# 11_Power-DC_IN.net
KiCad netlist of a schematic drawn in Altium Designer
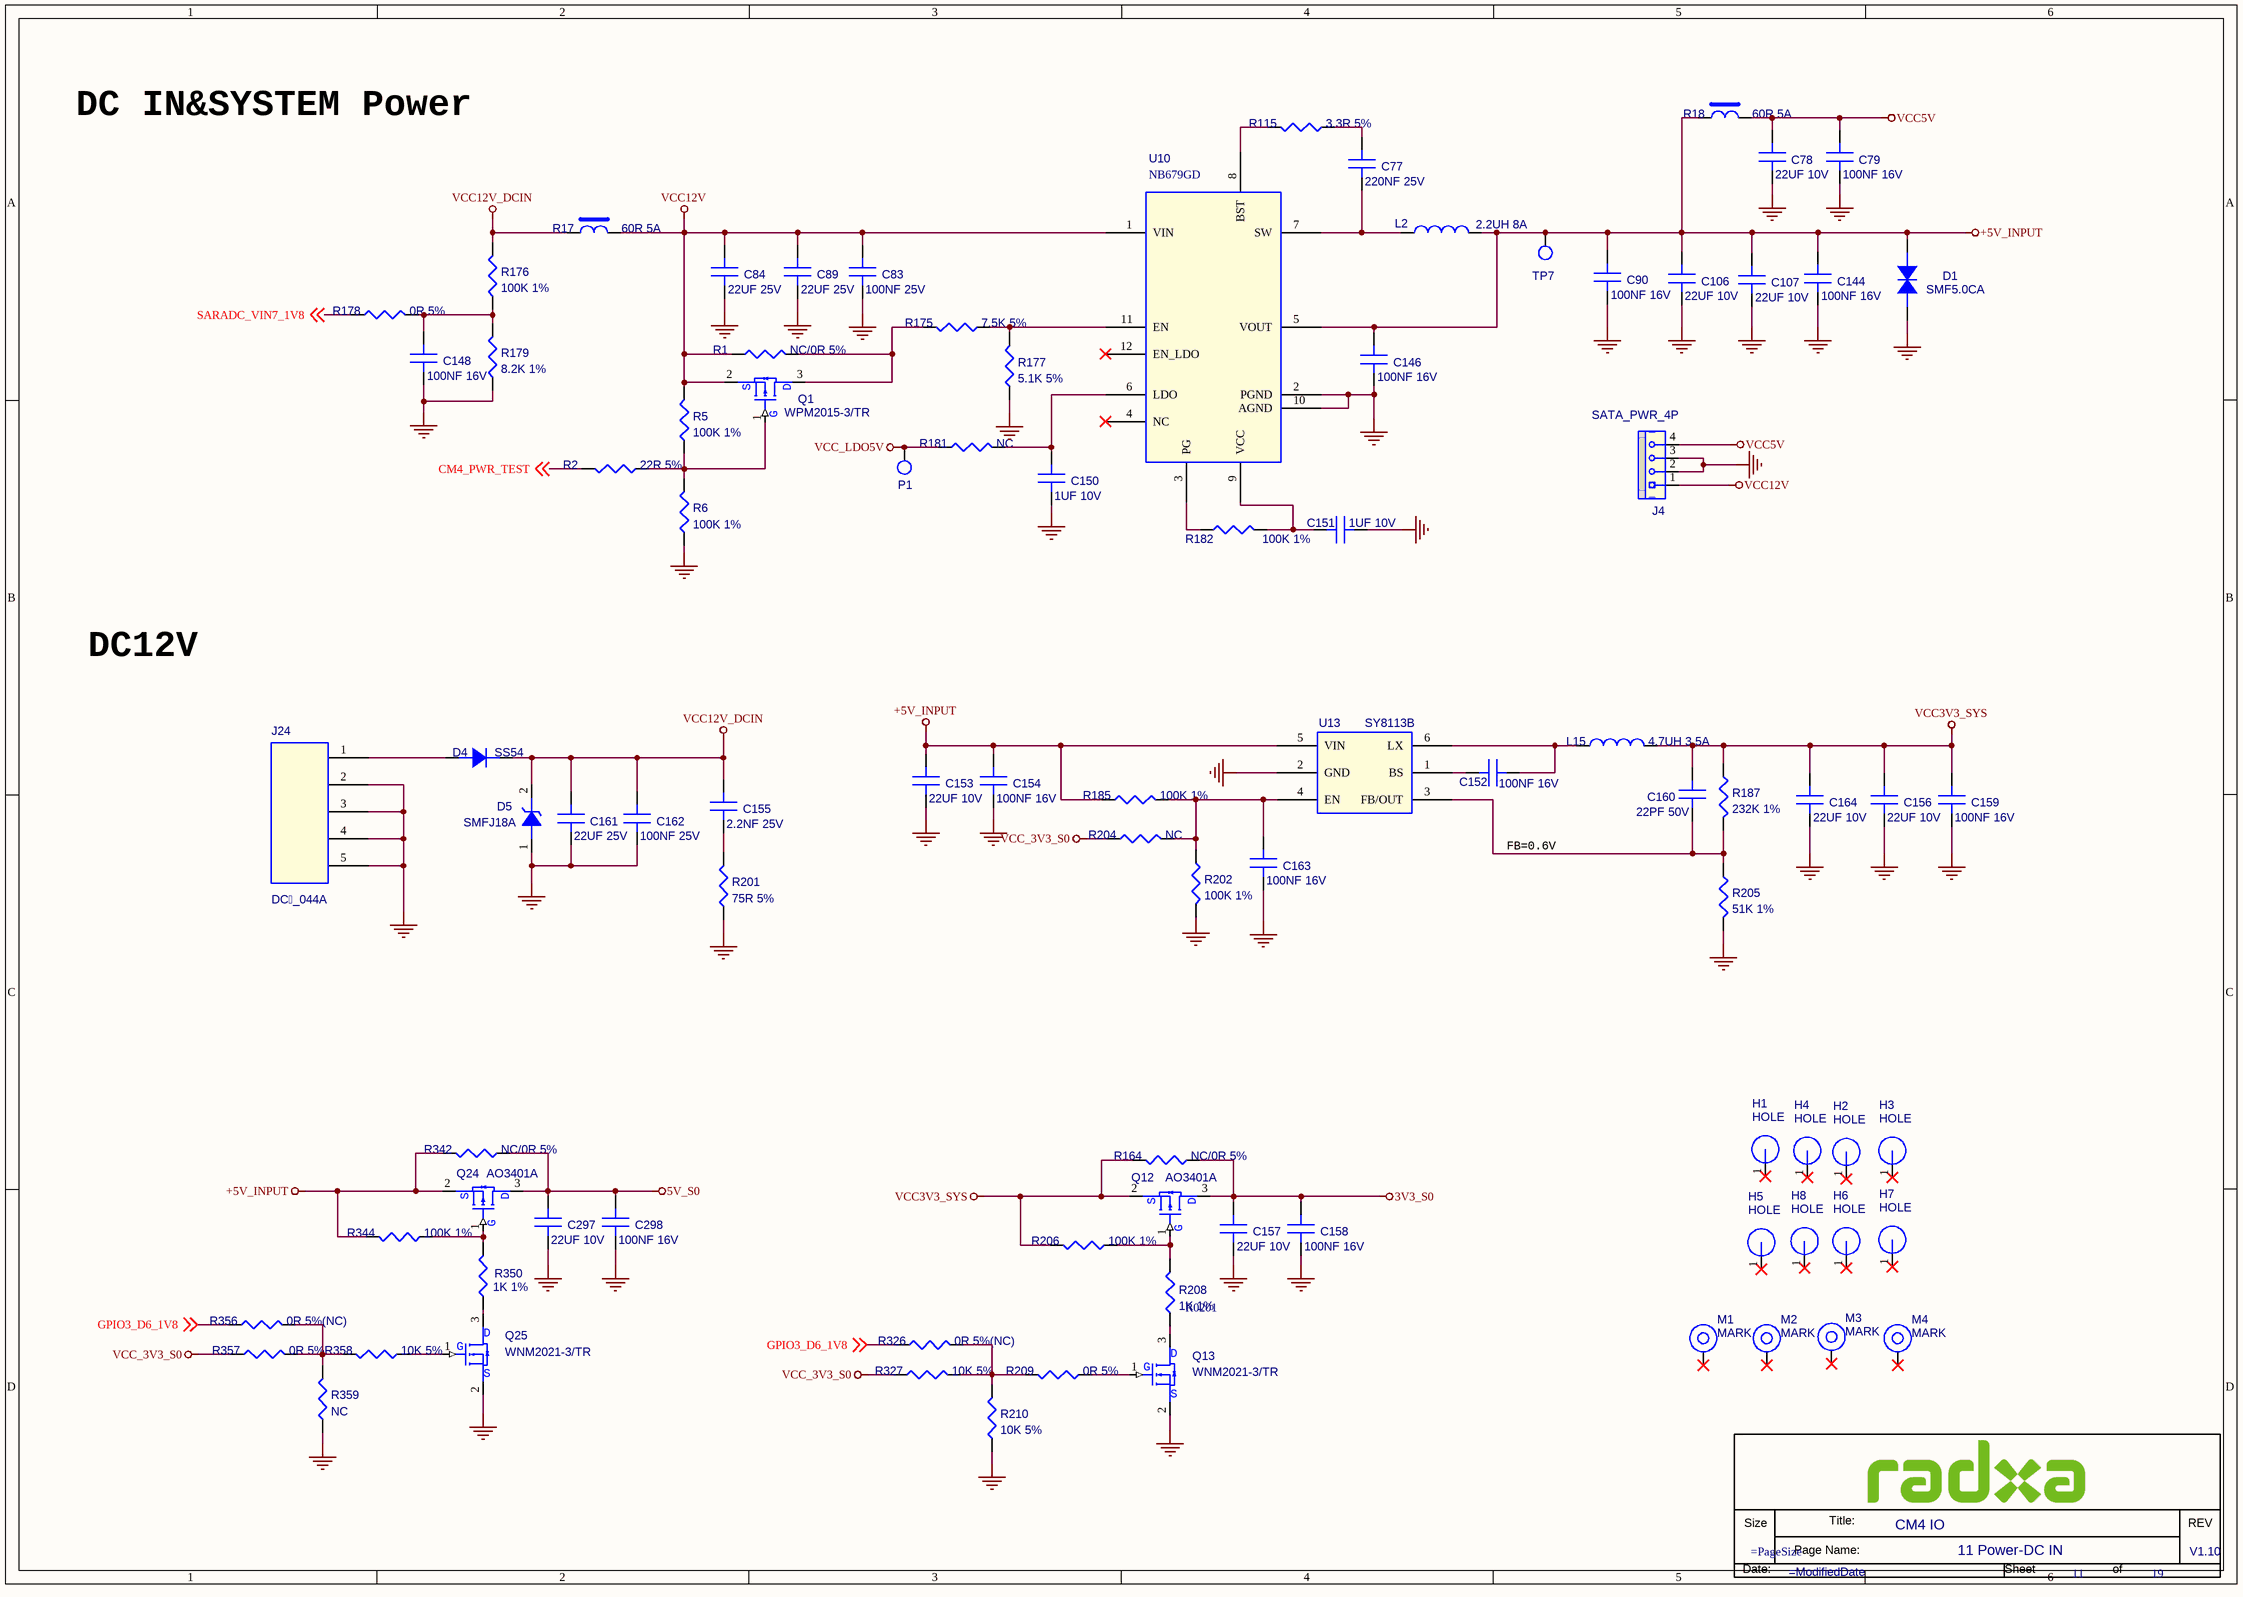
[diagram p0: 11 Power-DC IN.SchDoc]

(export (version "E")
  (design (tool "Eeschema 10.0.6"))
  (components
    (comp (ref "C77")
      (value "220NF 25V")
      (footprint "C0201")
      (description "SMD  0201  220NF  25V  X5R  ±10%  ROHS")
      (fields (field (name "PART NUMBER") "A1C01.00365"))
      (libsource (lib "*") (part "C"))
    )
    (comp (ref "C78")
      (value "22UF 10V")
      (footprint "C0603")
      (description "SMD  0603  22UF  10V  X5R  ±20%  ROHS")
      (fields (field (name "PART NUMBER") "A1C01.00015"))
      (libsource (lib "*") (part "C"))
    )
    (comp (ref "C79")
      (value "100NF 16V")
      (footprint "C0201")
      (description "SMD  0201  100NF  16V  X5R  ±20%  ROHS")
      (fields (field (name "PART NUMBER") "A1C01.00099"))
      (libsource (lib "*") (part "C"))
    )
    (comp (ref "C83")
      (value "100NF 25V")
      (footprint "C0201")
      (description "SMD  0201  100NF  25V  X5R  ±20%  ROHS")
      (fields (field (name "PART NUMBER") "A1C01.00101"))
      (libsource (lib "*") (part "C"))
    )
    (comp (ref "C84")
      (value "22UF 25V")
      (footprint "C0805")
      (description "SMD  0805  22UF  25V  X5R  ±20%  ROHS")
      (fields (field (name "PART NUMBER") "A1C01.00249"))
      (libsource (lib "*") (part "C"))
    )
    (comp (ref "C89")
      (value "22UF 25V")
      (footprint "C0805")
      (description "SMD  0805  22UF  25V  X5R  ±20%  ROHS")
      (fields (field (name "PART NUMBER") "A1C01.00249"))
      (libsource (lib "*") (part "C"))
    )
    (comp (ref "C90")
      (value "100NF 16V")
      (footprint "C0201")
      (description "SMD  0201  100NF  16V  X5R  ±20%  ROHS")
      (fields (field (name "PART NUMBER") "A1C01.00099"))
      (libsource (lib "*") (part "C"))
    )
    (comp (ref "C106")
      (value "22UF 10V")
      (footprint "C0603")
      (description "SMD  0603  22UF  10V  X5R  ±20%  ROHS")
      (fields (field (name "PART NUMBER") "A1C01.00015"))
      (libsource (lib "*") (part "C"))
    )
    (comp (ref "C107")
      (value "22UF 10V")
      (footprint "C0603")
      (description "SMD  0603  22UF  10V  X5R  ±20%  ROHS")
      (fields (field (name "PART NUMBER") "A1C01.00015"))
      (libsource (lib "*") (part "C"))
    )
    (comp (ref "C144")
      (value "100NF 16V")
      (footprint "C0201")
      (description "SMD  0201  100NF  16V  X5R  ±20%  ROHS")
      (fields (field (name "PART NUMBER") "A1C01.00099"))
      (libsource (lib "*") (part "C"))
    )
    (comp (ref "C146")
      (value "100NF 16V")
      (footprint "C0201")
      (description "SMD  0201  100NF  16V  X5R  ±20%  ROHS")
      (fields (field (name "PART NUMBER") "A1C01.00099"))
      (libsource (lib "*") (part "C"))
    )
    (comp (ref "C148")
      (value "100NF 16V")
      (footprint "C0201")
      (description "SMD  0201  100NF  16V  X5R  ±20%  ROHS")
      (fields (field (name "PART NUMBER") "A1C01.00099"))
      (libsource (lib "*") (part "C"))
    )
    (comp (ref "C150")
      (value "1UF 10V")
      (footprint "C0201")
      (description "SMD  0201  1UF  10V  X5R  ±20%  ROHS")
      (fields (field (name "PART NUMBER") "A1C01.00081"))
      (libsource (lib "*") (part "C"))
    )
    (comp (ref "C151")
      (value "1UF 10V")
      (footprint "C0201")
      (description "SMD  0201  1UF  10V  X5R  ±20%  ROHS")
      (fields (field (name "PART NUMBER") "A1C01.00081"))
      (libsource (lib "*") (part "C"))
    )
    (comp (ref "C152")
      (value "100NF 16V")
      (footprint "C0201")
      (description "SMD  0201  100NF  16V  X5R  ±20%  ROHS")
      (fields (field (name "PART NUMBER") "A1C01.00099"))
      (libsource (lib "*") (part "C"))
    )
    (comp (ref "C153")
      (value "22UF 10V")
      (footprint "C0603")
      (description "SMD  0603  22UF  10V  X5R  ±20%  ROHS")
      (fields (field (name "PART NUMBER") "A1C01.00015"))
      (libsource (lib "*") (part "C"))
    )
    (comp (ref "C154")
      (value "100NF 16V")
      (footprint "C0201")
      (description "SMD  0201  100NF  16V  X5R  ±20%  ROHS")
      (fields (field (name "PART NUMBER") "A1C01.00099"))
      (libsource (lib "*") (part "C"))
    )
    (comp (ref "C155")
      (value "2.2NF 25V")
      (footprint "C0201")
      (description "SMD  0201  2.2NF  25V  X7R  ±10%  ROHS")
      (fields (field (name "PART NUMBER") "A1C01.00123"))
      (libsource (lib "*") (part "C"))
    )
    (comp (ref "C156")
      (value "22UF 10V")
      (footprint "C0603")
      (description "SMD  0603  22UF  10V  X5R  ±20%  ROHS")
      (fields (field (name "PART NUMBER") "A1C01.00015"))
      (libsource (lib "*") (part "C"))
    )
    (comp (ref "C157")
      (value "22UF 10V")
      (footprint "C0603")
      (description "SMD  0603  22UF  10V  X5R  ±20%  ROHS")
      (fields (field (name "PART NUMBER") "A1C01.00015"))
      (libsource (lib "*") (part "C"))
    )
    (comp (ref "C158")
      (value "100NF 16V")
      (footprint "C0201")
      (description "SMD  0201  100NF  16V  X5R  ±20%  ROHS")
      (fields (field (name "PART NUMBER") "A1C01.00099"))
      (libsource (lib "*") (part "C"))
    )
    (comp (ref "C159")
      (value "100NF 16V")
      (footprint "C0201")
      (description "SMD  0201  100NF  16V  X5R  ±20%  ROHS")
      (fields (field (name "PART NUMBER") "A1C01.00099"))
      (libsource (lib "*") (part "C"))
    )
    (comp (ref "C160")
      (value "22PF 50V")
      (footprint "C0201")
      (description "SMD  0201  22PF  50V  NPO  ±5%  ROHS")
      (fields (field (name "PART NUMBER") "A1C01.00021"))
      (libsource (lib "*") (part "C"))
    )
    (comp (ref "C161")
      (value "22UF 25V")
      (footprint "C0805")
      (description "SMD  0805  22UF  25V  X5R  ±20%  ROHS")
      (fields (field (name "PART NUMBER") "A1C01.00249"))
      (libsource (lib "*") (part "C"))
    )
    (comp (ref "C162")
      (value "100NF 25V")
      (footprint "C0201")
      (description "SMD  0201  100NF  25V  X5R  ±20%  ROHS")
      (fields (field (name "PART NUMBER") "A1C01.00101"))
      (libsource (lib "*") (part "C"))
    )
    (comp (ref "C163")
      (value "100NF 16V")
      (footprint "C0201")
      (description "SMD  0201  100NF  16V  X5R  ±20%  ROHS")
      (fields (field (name "PART NUMBER") "A1C01.00099"))
      (libsource (lib "*") (part "C"))
    )
    (comp (ref "C164")
      (value "22UF 10V")
      (footprint "C0603")
      (description "SMD  0603  22UF  10V  X5R  ±20%  ROHS")
      (fields (field (name "PART NUMBER") "A1C01.00015"))
      (libsource (lib "*") (part "C"))
    )
    (comp (ref "C297")
      (value "22UF 10V")
      (footprint "C0603")
      (description "SMD  0603  22UF  10V  X5R  ±20%  ROHS")
      (fields (field (name "PART NUMBER") "A1C01.00015"))
      (libsource (lib "*") (part "C"))
    )
    (comp (ref "C298")
      (value "100NF 16V")
      (footprint "C0201")
      (description "SMD  0201  100NF  16V  X5R  ±20%  ROHS")
      (fields (field (name "PART NUMBER") "A1C01.00099"))
      (libsource (lib "*") (part "C"))
    )
    (comp (ref "D1")
      (value "SMF5.0CA")
      (footprint "SOD_123")
      (description "SMD  SOD-123FL  SMF5.0CA  晶导微  ROHS")
      (fields (field (name "PART NUMBER") "A1D02.00132"))
      (libsource (lib "*") (part "DIODE_S"))
    )
    (comp (ref "D4")
      (value "SS54")
      (footprint "DO_214AC")
      (description "SMD  编带  DO-214AC  SS54  晶导微  ROHS")
      (fields
        (field (name "MANUFACTURER") "星海")
        (field (name "PART NUMBER") "A1D02.00006")
        (field (name "CREATED BY") "JJJ")
      )
      (libsource (lib "*") (part "DIODE"))
    )
    (comp (ref "D5")
      (value "SMFJ18A")
      (footprint "SOD_123")
      (description "SMD  编带  SOD-123  SMFJ18A  晶导微电子  ROHS")
      (fields (field (name "PART NUMBER") "A1D02.00007"))
      (libsource (lib "*") (part "TVS"))
    )
    (comp (ref "H1")
      (value "HOLE")
      (footprint "H3.8MM")
      (description "直径3.5mm hole")
      (fields (field (name "CREATED BY") "CZD"))
      (libsource (lib "*") (part "HOLE"))
    )
    (comp (ref "H2")
      (value "HOLE")
      (footprint "H3.8MM")
      (description "直径3.5mm hole")
      (fields (field (name "CREATED BY") "CZD"))
      (libsource (lib "*") (part "HOLE"))
    )
    (comp (ref "H3")
      (value "HOLE")
      (footprint "H3.8MM")
      (description "直径3.5mm hole")
      (fields (field (name "CREATED BY") "CZD"))
      (libsource (lib "*") (part "HOLE"))
    )
    (comp (ref "H4")
      (value "HOLE")
      (footprint "H3.8MM")
      (description "直径3.5mm hole")
      (fields (field (name "CREATED BY") "CZD"))
      (libsource (lib "*") (part "HOLE"))
    )
    (comp (ref "H5")
      (value "HOLE")
      (footprint "H3.8MM")
      (description "直径3.5mm hole")
      (fields (field (name "CREATED BY") "CZD"))
      (libsource (lib "*") (part "HOLE"))
    )
    (comp (ref "H6")
      (value "HOLE")
      (footprint "H3.8MM")
      (description "直径3.5mm hole")
      (fields (field (name "CREATED BY") "CZD"))
      (libsource (lib "*") (part "HOLE"))
    )
    (comp (ref "H7")
      (value "HOLE")
      (footprint "H3.8MM")
      (description "直径3.5mm hole")
      (fields (field (name "CREATED BY") "CZD"))
      (libsource (lib "*") (part "HOLE"))
    )
    (comp (ref "H8")
      (value "HOLE")
      (footprint "H3.8MM")
      (description "直径3.5mm hole")
      (fields (field (name "CREATED BY") "CZD"))
      (libsource (lib "*") (part "HOLE"))
    )
    (comp (ref "J4")
      (value "SATA_PWR_4P")
      (footprint "CON_TH1X4_2D54_SATA")
      (description "DIP  排针座  1*4PIN  180度  无定位柱  2.54mm脚距  针长一端8.3mm  另一端3.5mm  小4PIN  白色  M2545V-4P  兴飞  ROHS")
      (fields (field (name "PART NUMBER") "A1J01.00014"))
      (libsource (lib "*") (part "SATA_PWR_4P"))
    )
    (comp (ref "J24")
      (value "DC_044A")
      (footprint "DC_TH5_12X10")
      (description "DIP  5PIN  DS-044BS  内孔Φ6mm  铁芯Φ2.0mm  11.6*10.2*7.3mm  协佳  ROHS")
      (fields (field (name "PART NUMBER") "A1J11.00007"))
      (libsource (lib "*") (part "DC_044A_5520"))
    )
    (comp (ref "L2")
      (value "2.2UH 8A")
      (footprint "L_6050")
      (description "SMD  带屏蔽  7.2x6.6x5mm  2.2UH  8A  ±20%  RXWSHC0650-2R2M  仁芯微  ROHS")
      (fields (field (name "PART NUMBER") "A1L01.00163"))
      (libsource (lib "*") (part "L"))
    )
    (comp (ref "L15")
      (value "4.7UH 3.5A")
      (footprint "L_5020")
      (description "SMD  带屏蔽  5.4*5.2*1.8mm  4.7UH  3.5A  ±20%  RXWSHC0520-4R7M  仁芯微  ROHS")
      (fields (field (name "PART NUMBER") "A1L01.00071"))
      (libsource (lib "*") (part "L"))
    )
    (comp (ref "M1")
      (value "MARK")
      (footprint "MARK")
      (description "MARK Symble")
      (fields (field (name "CREATED BY") "JJJ"))
      (libsource (lib "*") (part "MARK"))
    )
    (comp (ref "M2")
      (value "MARK")
      (footprint "MARK")
      (description "MARK Symble")
      (fields (field (name "CREATED BY") "JJJ"))
      (libsource (lib "*") (part "MARK"))
    )
    (comp (ref "M3")
      (value "MARK")
      (footprint "MARK")
      (description "MARK Symble")
      (fields (field (name "CREATED BY") "JJJ"))
      (libsource (lib "*") (part "MARK"))
    )
    (comp (ref "M4")
      (value "MARK")
      (footprint "MARK")
      (description "MARK Symble")
      (fields (field (name "CREATED BY") "JJJ"))
      (libsource (lib "*") (part "MARK"))
    )
    (comp (ref "P1") (value "TEST") (footprint "TEST") (libsource (lib "*") (part "TESTPOINT1")))
    (comp (ref "Q1")
      (value "WPM2015-3/TR")
      (footprint "SOT_23")
      (description "SMD编带  SOT-23  WPM2015-3/TR  P沟道  ROHS")
      (fields (field (name "PART NUMBER") "A1D01.00019"))
      (libsource (lib "*") (part "MOSFET_PNP"))
    )
    (comp (ref "Q12")
      (value "AO3401A")
      (footprint "SOT_23")
      (description "SMD  编带  SOT23-3  AO3401A  P沟道  AOS  ROHS")
      (fields (field (name "PART NUMBER") "A1D01.00034"))
      (libsource (lib "*") (part "MOSFET_PNP"))
    )
    (comp (ref "Q13")
      (value "WNM2021-3/TR")
      (footprint "SOT_323")
      (description "SMD编带  SOT-323  WILLSEMI(韦尔)  WNM2021-3/TR  N沟道  ROHS")
      (fields (field (name "PART NUMBER") "A1D01.00008"))
      (libsource (lib "*") (part "MOSFET_NPN"))
    )
    (comp (ref "Q24")
      (value "AO3401A")
      (footprint "SOT_23")
      (description "SMD  编带  SOT23-3  AO3401A  P沟道  AOS  ROHS")
      (fields (field (name "PART NUMBER") "A1D01.00034"))
      (libsource (lib "*") (part "MOSFET_PNP"))
    )
    (comp (ref "Q25")
      (value "WNM2021-3/TR")
      (footprint "SOT_323")
      (description "SMD编带  SOT-323  WILLSEMI(韦尔)  WNM2021-3/TR  N沟道  ROHS")
      (fields (field (name "PART NUMBER") "A1D01.00008"))
      (libsource (lib "*") (part "MOSFET_NPN"))
    )
    (comp (ref "R1")
      (value "NC/0R 5%")
      (footprint "R0402")
      (description "SMD  0201  0R  1/20W  ±5%  ROHS")
      (fields (field (name "PART NUMBER") "A1R01.00027"))
      (libsource (lib "*") (part "R"))
    )
    (comp (ref "R2")
      (value "22R 5%")
      (footprint "R0402")
      (description "SMD  0201  22R  1/20W  ±5%  ROHS")
      (fields (field (name "PART NUMBER") "A1R01.00024"))
      (libsource (lib "*") (part "R"))
    )
    (comp (ref "R5")
      (value "100K 1%")
      (footprint "R0402")
      (description "SMD  0201  100K  1/20W  ±1%  ROHS")
      (fields (field (name "PART NUMBER") "A1R01.00165"))
      (libsource (lib "*") (part "R"))
    )
    (comp (ref "R6")
      (value "100K 1%")
      (footprint "R0402")
      (description "SMD  0201  100K  1/20W  ±1%  ROHS")
      (fields (field (name "PART NUMBER") "A1R01.00165"))
      (libsource (lib "*") (part "R"))
    )
    (comp (ref "R17")
      (value "60R 5A")
      (footprint "FB1206")
      (description "SMD  1206  FB60R  5A  ±25%  ROHS")
      (fields (field (name "PART NUMBER") "A1L09.00006"))
      (libsource (lib "*") (part "BEAD"))
    )
    (comp (ref "R18")
      (value "60R 5A")
      (footprint "FB1206")
      (description "SMD  1206  FB60R  5A  ±25%  ROHS")
      (fields (field (name "PART NUMBER") "A1L09.00006"))
      (libsource (lib "*") (part "BEAD"))
    )
    (comp (ref "R115")
      (value "3.3R 5%")
      (footprint "R0402")
      (description "SMD  0201  3.3R  1/20W  ±5%  ROHS")
      (fields (field (name "PART NUMBER") "A1R01.00145"))
      (libsource (lib "*") (part "R"))
    )
    (comp (ref "R164")
      (value "NC/0R 5%")
      (footprint "R0402")
      (description "SMD  0402  0R  1/16W  ±5%  ROHS")
      (fields (field (name "PART NUMBER") "A1R01.00030"))
      (libsource (lib "*") (part "R"))
    )
    (comp (ref "R175")
      (value "7.5K 5%")
      (footprint "R0402")
      (description "SMD  0201  7.5K  1/20W  ±5%  ROHS")
      (fields (field (name "PART NUMBER") "A1R01.00495"))
      (libsource (lib "*") (part "R"))
    )
    (comp (ref "R176")
      (value "100K 1%")
      (footprint "R0402")
      (description "SMD  0201  100K  1/20W  ±1%  ROHS")
      (fields (field (name "PART NUMBER") "A1R01.00165"))
      (libsource (lib "*") (part "R"))
    )
    (comp (ref "R177")
      (value "5.1K 5%")
      (footprint "R0402")
      (description "SMD  0201  5.1K  1/20W  ±5%  ROHS")
      (fields (field (name "PART NUMBER") "A1R01.00013"))
      (libsource (lib "*") (part "R"))
    )
    (comp (ref "R178")
      (value "0R 5%")
      (footprint "R0402")
      (description "SMD  0201  0R  1/20W  ±5%  ROHS")
      (fields (field (name "PART NUMBER") "A1R01.00027"))
      (libsource (lib "*") (part "R"))
    )
    (comp (ref "R179")
      (value "8.2K 1%")
      (footprint "R0402")
      (description "SMD  0201  8.2K  1/20W  ±1%  ROHS")
      (fields (field (name "PART NUMBER") "A1R01.00086"))
      (libsource (lib "*") (part "R"))
    )
    (comp (ref "R181")
      (value "NC")
      (footprint "R0402")
      (description "SMD  0201  0R  1/20W  ±5%  ROHS")
      (fields (field (name "PART NUMBER") "A1R01.00027"))
      (libsource (lib "*") (part "R"))
    )
    (comp (ref "R182")
      (value "100K 1%")
      (footprint "R0402")
      (description "SMD  0201  100K  1/20W  ±1%  ROHS")
      (fields (field (name "PART NUMBER") "A1R01.00165"))
      (libsource (lib "*") (part "R"))
    )
    (comp (ref "R185")
      (value "100K 1%")
      (footprint "R0402")
      (description "SMD  0201  100K  1/20W  ±1%  ROHS")
      (fields (field (name "PART NUMBER") "A1R01.00165"))
      (libsource (lib "*") (part "R"))
    )
    (comp (ref "R187")
      (value "232K 1%")
      (footprint "R0402")
      (description "SMD  0201  232K  1/20W  ±1%  ROHS")
      (fields (field (name "PART NUMBER") "A1R01.00189"))
      (libsource (lib "*") (part "R"))
    )
    (comp (ref "R201")
      (value "75R 5%")
      (footprint "R0402")
      (description "SMD  0201  75R  1/20W  ±5%  ROHS")
      (fields (field (name "PART NUMBER") "A1R01.00395"))
      (libsource (lib "*") (part "R"))
    )
    (comp (ref "R202")
      (value "100K 1%")
      (footprint "R0402")
      (description "SMD  0201  100K  1/20W  ±1%  ROHS")
      (fields (field (name "PART NUMBER") "A1R01.00165"))
      (libsource (lib "*") (part "R"))
    )
    (comp (ref "R204")
      (value "NC")
      (footprint "R0402")
      (description "SMD  0201  10K  1/20W  ±5%  ROHS")
      (fields (field (name "PART NUMBER") "A1R01.00012"))
      (libsource (lib "*") (part "R"))
    )
    (comp (ref "R205")
      (value "51K 1%")
      (footprint "R0402")
      (description "SMD  0201  51K  1/20W  ±1%  ROHS")
      (fields (field (name "PART NUMBER") "A1R01.00149"))
      (libsource (lib "*") (part "R"))
    )
    (comp (ref "R206")
      (value "100K 1%")
      (footprint "R0402")
      (description "SMD  0201  100K  1/20W  ±1%  ROHS")
      (fields (field (name "PART NUMBER") "A1R01.00165"))
      (libsource (lib "*") (part "R"))
    )
    (comp (ref "R208")
      (value "1K 1%")
      (footprint "R0402")
      (description "SMD  0201  1K  1/20W  ±1%  ROHS")
      (fields (field (name "PCB FOOTPRINT") "R0201") (field (name "PART NUMBER") "A1R01.00111"))
      (libsource (lib "*") (part "R"))
    )
    (comp (ref "R209")
      (value "0R 5%")
      (footprint "R0402")
      (description "SMD  0201  10K  1/20W  ±5%  ROHS")
      (fields (field (name "PART NUMBER") "A1R01.00012"))
      (libsource (lib "*") (part "R"))
    )
    (comp (ref "R210")
      (value "10K 5%")
      (footprint "R0402")
      (description "SMD  0201  10K  1/20W  ±5%  ROHS")
      (fields (field (name "PART NUMBER") "A1R01.00012"))
      (libsource (lib "*") (part "R"))
    )
    (comp (ref "R326")
      (value "0R 5%(NC)")
      (footprint "R0402")
      (description "SMD  0201  0R  1/20W  ±5%  ROHS")
      (fields (field (name "PART NUMBER") "A1R01.00027"))
      (libsource (lib "*") (part "R"))
    )
    (comp (ref "R327")
      (value "10K 5%")
      (footprint "R0402")
      (description "SMD  0201  0R  1/20W  ±5%  ROHS")
      (fields (field (name "PART NUMBER") "A1R01.00027"))
      (libsource (lib "*") (part "R"))
    )
    (comp (ref "R342")
      (value "NC/0R 5%")
      (footprint "R0402")
      (description "SMD  0402  0R  1/16W  ±5%  ROHS")
      (fields (field (name "PART NUMBER") "A1R01.00030"))
      (libsource (lib "*") (part "R"))
    )
    (comp (ref "R344")
      (value "100K 1%")
      (footprint "R0402")
      (description "SMD  0201  100K  1/20W  ±1%  ROHS")
      (fields (field (name "PART NUMBER") "A1R01.00165"))
      (libsource (lib "*") (part "R"))
    )
    (comp (ref "R350")
      (value "1K 1%")
      (footprint "R0402")
      (description "SMD  0201  1K  1/20W  ±1%  ROHS")
      (fields (field (name "PART NUMBER") "A1R01.00111"))
      (libsource (lib "*") (part "R"))
    )
    (comp (ref "R356")
      (value "0R 5%(NC)")
      (footprint "R0402")
      (description "SMD  0201  0R  1/20W  ±5%  ROHS")
      (fields (field (name "PART NUMBER") "A1R01.00027"))
      (libsource (lib "*") (part "R"))
    )
    (comp (ref "R357")
      (value "0R 5%")
      (footprint "R0402")
      (description "SMD  0201  0R  1/20W  ±5%  ROHS")
      (fields (field (name "PART NUMBER") "A1R01.00027"))
      (libsource (lib "*") (part "R"))
    )
    (comp (ref "R358")
      (value "10K 5%")
      (footprint "R0402")
      (description "SMD  0201  10K  1/20W  ±5%  ROHS")
      (fields (field (name "PART NUMBER") "A1R01.00012"))
      (libsource (lib "*") (part "R"))
    )
    (comp (ref "R359")
      (value "NC")
      (footprint "R0402")
      (description "SMD  0201  10K  1/20W  ±5%  ROHS")
      (fields (field (name "PART NUMBER") "A1R01.00012"))
      (libsource (lib "*") (part "R"))
    )
    (comp (ref "TP7")
      (value "TP_0.7")
      (footprint "TEST")
      (description "Test Point 0.7mm")
      (fields (field (name "CREATED BY") "JJJ"))
      (libsource (lib "*") (part "TP"))
    )
    (comp (ref "U10")
      (value "NB679GD")
      (footprint "QFN12_0D5_2")
      (description "SMD  DCDC  NB679GD-Z  QFN12  MPS  ROHS")
      (fields (field (name "PART NUMBER") "A1I01.00033"))
      (libsource (lib "*") (part "NB679"))
    )
    (comp (ref "U13")
      (value "SY8113B")
      (footprint "SOT23_6")
      (description "SMD  DCDC  SY8113BADC  SOT23-6  silergy(矽力杰)  ROHS")
      (fields (field (name "PART NUMBER") "A1I01.00093"))
      (libsource (lib "*") (part "SY8113B"))
    )
  )
  (nets
    (net (code "1") (name "+5V_INPUT") (class "Default")
      (node (ref "C106") (pin "1") (pinfunction "A_1") (pintype "passive"))
      (node (ref "C107") (pin "1") (pinfunction "A_1") (pintype "passive"))
      (node (ref "C144") (pin "1") (pinfunction "A_1") (pintype "passive"))
      (node (ref "C146") (pin "1") (pinfunction "A_1") (pintype "passive"))
      (node (ref "C153") (pin "1") (pinfunction "A_1") (pintype "passive"))
      (node (ref "C154") (pin "1") (pinfunction "A_1") (pintype "passive"))
      (node (ref "C90") (pin "1") (pinfunction "A_1") (pintype "passive"))
      (node (ref "D1") (pin "2") (pinfunction "CATHODE_2") (pintype "passive"))
      (node (ref "L2") (pin "2") (pinfunction "2_2") (pintype "passive"))
      (node (ref "Q24") (pin "2") (pinfunction "S_2") (pintype "passive"))
      (node (ref "R18") (pin "1") (pinfunction "1_1") (pintype "passive"))
      (node (ref "R185") (pin "1") (pinfunction "1_1") (pintype "passive"))
      (node (ref "R342") (pin "2") (pinfunction "2_2") (pintype "passive"))
      (node (ref "R344") (pin "2") (pinfunction "2_2") (pintype "passive"))
      (node (ref "TP7") (pin "1") (pinfunction "1_1") (pintype "passive"))
      (node (ref "U10") (pin "5") (pinfunction "VOUT_5") (pintype "passive"))
      (node (ref "U13") (pin "5") (pinfunction "VIN_5") (pintype "passive"))
    )
    (net (code "2") (name "3V3_S0") (class "Default")
      (node (ref "C157") (pin "1") (pinfunction "A_1") (pintype "passive"))
      (node (ref "C158") (pin "1") (pinfunction "A_1") (pintype "passive"))
      (node (ref "Q12") (pin "3") (pinfunction "D_3") (pintype "passive"))
      (node (ref "R164") (pin "1") (pinfunction "1_1") (pintype "passive"))
    )
    (net (code "3") (name "5V_S0") (class "Default")
      (node (ref "C297") (pin "1") (pinfunction "A_1") (pintype "passive"))
      (node (ref "C298") (pin "1") (pinfunction "A_1") (pintype "passive"))
      (node (ref "Q24") (pin "3") (pinfunction "D_3") (pintype "passive"))
      (node (ref "R342") (pin "1") (pinfunction "1_1") (pintype "passive"))
    )
    (net (code "4") (name "CM4_PWR_TEST") (class "Default")
      (node (ref "R2") (pin "1") (pinfunction "1_1") (pintype "passive"))
    )
    (net (code "5") (name "GND") (class "Default")
      (node (ref "C106") (pin "2") (pinfunction "B_2") (pintype "passive"))
      (node (ref "C107") (pin "2") (pinfunction "B_2") (pintype "passive"))
      (node (ref "C144") (pin "2") (pinfunction "B_2") (pintype "passive"))
      (node (ref "C146") (pin "2") (pinfunction "B_2") (pintype "passive"))
      (node (ref "C148") (pin "2") (pinfunction "B_2") (pintype "passive"))
      (node (ref "C150") (pin "2") (pinfunction "B_2") (pintype "passive"))
      (node (ref "C151") (pin "2") (pinfunction "B_2") (pintype "passive"))
      (node (ref "C153") (pin "2") (pinfunction "B_2") (pintype "passive"))
      (node (ref "C154") (pin "2") (pinfunction "B_2") (pintype "passive"))
      (node (ref "C156") (pin "2") (pinfunction "B_2") (pintype "passive"))
      (node (ref "C157") (pin "2") (pinfunction "B_2") (pintype "passive"))
      (node (ref "C158") (pin "2") (pinfunction "B_2") (pintype "passive"))
      (node (ref "C159") (pin "2") (pinfunction "B_2") (pintype "passive"))
      (node (ref "C161") (pin "1") (pinfunction "A_1") (pintype "passive"))
      (node (ref "C162") (pin "2") (pinfunction "B_2") (pintype "passive"))
      (node (ref "C163") (pin "2") (pinfunction "B_2") (pintype "passive"))
      (node (ref "C164") (pin "2") (pinfunction "B_2") (pintype "passive"))
      (node (ref "C297") (pin "2") (pinfunction "B_2") (pintype "passive"))
      (node (ref "C298") (pin "2") (pinfunction "B_2") (pintype "passive"))
      (node (ref "C78") (pin "2") (pinfunction "B_2") (pintype "passive"))
      (node (ref "C79") (pin "2") (pinfunction "B_2") (pintype "passive"))
      (node (ref "C83") (pin "2") (pinfunction "B_2") (pintype "passive"))
      (node (ref "C84") (pin "2") (pinfunction "B_2") (pintype "passive"))
      (node (ref "C89") (pin "2") (pinfunction "B_2") (pintype "passive"))
      (node (ref "C90") (pin "2") (pinfunction "B_2") (pintype "passive"))
      (node (ref "D1") (pin "1") (pinfunction "ANODE_1") (pintype "passive"))
      (node (ref "D5") (pin "1") (pinfunction "ANODE_1") (pintype "passive"))
      (node (ref "J24") (pin "2") (pinfunction "2_2") (pintype "passive"))
      (node (ref "J24") (pin "3") (pinfunction "3_3") (pintype "passive"))
      (node (ref "J24") (pin "4") (pinfunction "4_4") (pintype "passive"))
      (node (ref "J24") (pin "5") (pinfunction "5_5") (pintype "passive"))
      (node (ref "J4") (pin "2") (pinfunction "2_2") (pintype "passive"))
      (node (ref "J4") (pin "3") (pinfunction "3_3") (pintype "passive"))
      (node (ref "Q13") (pin "2") (pinfunction "S_2") (pintype "passive"))
      (node (ref "Q25") (pin "2") (pinfunction "S_2") (pintype "passive"))
      (node (ref "R177") (pin "1") (pinfunction "1_1") (pintype "passive"))
      (node (ref "R179") (pin "1") (pinfunction "1_1") (pintype "passive"))
      (node (ref "R201") (pin "1") (pinfunction "1_1") (pintype "passive"))
      (node (ref "R202") (pin "2") (pinfunction "2_2") (pintype "passive"))
      (node (ref "R205") (pin "2") (pinfunction "2_2") (pintype "passive"))
      (node (ref "R210") (pin "2") (pinfunction "2_2") (pintype "passive"))
      (node (ref "R359") (pin "2") (pinfunction "2_2") (pintype "passive"))
      (node (ref "R6") (pin "1") (pinfunction "1_1") (pintype "passive"))
      (node (ref "U10") (pin "10") (pinfunction "AGND_10") (pintype "passive"))
      (node (ref "U10") (pin "2") (pinfunction "PGND_2") (pintype "passive"))
      (node (ref "U13") (pin "2") (pinfunction "GND_2") (pintype "passive"))
    )
    (net (code "6") (name "GPIO3_D6_1V8") (class "Default")
      (node (ref "R326") (pin "1") (pinfunction "1_1") (pintype "passive"))
      (node (ref "R356") (pin "1") (pinfunction "1_1") (pintype "passive"))
    )
    (net (code "7") (name "Net-(C77-A)") (class "Default")
      (node (ref "C77") (pin "1") (pinfunction "A_1") (pintype "passive"))
      (node (ref "R115") (pin "2") (pinfunction "2_2") (pintype "passive"))
    )
    (net (code "8") (name "Net-(C77-B)") (class "Default")
      (node (ref "C77") (pin "2") (pinfunction "B_2") (pintype "passive"))
      (node (ref "L2") (pin "1") (pinfunction "1_1") (pintype "passive"))
      (node (ref "U10") (pin "7") (pinfunction "SW_7") (pintype "passive"))
    )
    (net (code "9") (name "Net-(C148-A)") (class "Default")
      (node (ref "C148") (pin "1") (pinfunction "A_1") (pintype "passive"))
      (node (ref "R176") (pin "1") (pinfunction "1_1") (pintype "passive"))
      (node (ref "R178") (pin "2") (pinfunction "2_2") (pintype "passive"))
      (node (ref "R179") (pin "2") (pinfunction "2_2") (pintype "passive"))
    )
    (net (code "10") (name "Net-(C150-A)") (class "Default")
      (node (ref "C150") (pin "1") (pinfunction "A_1") (pintype "passive"))
      (node (ref "R181") (pin "2") (pinfunction "2_2") (pintype "passive"))
      (node (ref "U10") (pin "6") (pinfunction "LDO_6") (pintype "passive"))
    )
    (net (code "11") (name "Net-(C151-A)") (class "Default")
      (node (ref "C151") (pin "1") (pinfunction "A_1") (pintype "passive"))
      (node (ref "R182") (pin "2") (pinfunction "2_2") (pintype "passive"))
      (node (ref "U10") (pin "9") (pinfunction "VCC_9") (pintype "passive"))
    )
    (net (code "12") (name "Net-(C152-A)") (class "Default")
      (node (ref "C152") (pin "1") (pinfunction "A_1") (pintype "passive"))
      (node (ref "U13") (pin "1") (pinfunction "BS_1") (pintype "passive"))
    )
    (net (code "13") (name "Net-(C152-B)") (class "Default")
      (node (ref "C152") (pin "2") (pinfunction "B_2") (pintype "passive"))
      (node (ref "L15") (pin "1") (pinfunction "1_1") (pintype "passive"))
      (node (ref "U13") (pin "6") (pinfunction "LX_6") (pintype "passive"))
    )
    (net (code "14") (name "Net-(C155-B)") (class "Default")
      (node (ref "C155") (pin "2") (pinfunction "B_2") (pintype "passive"))
      (node (ref "R201") (pin "2") (pinfunction "2_2") (pintype "passive"))
    )
    (net (code "15") (name "Net-(C160-B)") (class "Default")
      (node (ref "C160") (pin "2") (pinfunction "B_2") (pintype "passive"))
      (node (ref "R187") (pin "2") (pinfunction "2_2") (pintype "passive"))
      (node (ref "R205") (pin "1") (pinfunction "1_1") (pintype "passive"))
      (node (ref "U13") (pin "3") (pinfunction "FB/OUT_3") (pintype "passive"))
    )
    (net (code "16") (name "Net-(C163-A)") (class "Default")
      (node (ref "C163") (pin "1") (pinfunction "A_1") (pintype "passive"))
      (node (ref "R185") (pin "2") (pinfunction "2_2") (pintype "passive"))
      (node (ref "R202") (pin "1") (pinfunction "1_1") (pintype "passive"))
      (node (ref "R204") (pin "2") (pinfunction "2_2") (pintype "passive"))
      (node (ref "U13") (pin "4") (pinfunction "EN_4") (pintype "passive"))
    )
    (net (code "17") (name "Net-(D4-A)") (class "Default")
      (node (ref "D4") (pin "1") (pinfunction "A_1") (pintype "passive"))
      (node (ref "J24") (pin "1") (pinfunction "1_1") (pintype "passive"))
    )
    (net (code "18") (name "Net-(Q1-D)") (class "Default")
      (node (ref "Q1") (pin "3") (pinfunction "D_3") (pintype "passive"))
      (node (ref "R1") (pin "2") (pinfunction "2_2") (pintype "passive"))
      (node (ref "R175") (pin "2") (pinfunction "2_2") (pintype "passive"))
    )
    (net (code "19") (name "Net-(Q1-G)") (class "Default")
      (node (ref "Q1") (pin "1") (pinfunction "G_1") (pintype "input"))
      (node (ref "R2") (pin "2") (pinfunction "2_2") (pintype "passive"))
      (node (ref "R5") (pin "1") (pinfunction "1_1") (pintype "passive"))
      (node (ref "R6") (pin "2") (pinfunction "2_2") (pintype "passive"))
    )
    (net (code "20") (name "Net-(Q12-G)") (class "Default")
      (node (ref "Q12") (pin "1") (pinfunction "G_1") (pintype "input"))
      (node (ref "R206") (pin "1") (pinfunction "1_1") (pintype "passive"))
      (node (ref "R208") (pin "1") (pinfunction "1_1") (pintype "passive"))
    )
    (net (code "21") (name "Net-(Q13-D)") (class "Default")
      (node (ref "Q13") (pin "3") (pinfunction "D_3") (pintype "passive"))
      (node (ref "R208") (pin "2") (pinfunction "2_2") (pintype "passive"))
    )
    (net (code "22") (name "Net-(Q13-G)") (class "Default")
      (node (ref "Q13") (pin "1") (pinfunction "G_1") (pintype "input"))
      (node (ref "R209") (pin "1") (pinfunction "1_1") (pintype "passive"))
    )
    (net (code "23") (name "Net-(Q24-G)") (class "Default")
      (node (ref "Q24") (pin "1") (pinfunction "G_1") (pintype "input"))
      (node (ref "R344") (pin "1") (pinfunction "1_1") (pintype "passive"))
      (node (ref "R350") (pin "1") (pinfunction "1_1") (pintype "passive"))
    )
    (net (code "24") (name "Net-(Q25-D)") (class "Default")
      (node (ref "Q25") (pin "3") (pinfunction "D_3") (pintype "passive"))
      (node (ref "R350") (pin "2") (pinfunction "2_2") (pintype "passive"))
    )
    (net (code "25") (name "Net-(Q25-G)") (class "Default")
      (node (ref "Q25") (pin "1") (pinfunction "G_1") (pintype "input"))
      (node (ref "R358") (pin "1") (pinfunction "1_1") (pintype "passive"))
    )
    (net (code "26") (name "Net-(R209-Pad2)") (class "Default")
      (node (ref "R209") (pin "2") (pinfunction "2_2") (pintype "passive"))
      (node (ref "R210") (pin "1") (pinfunction "1_1") (pintype "passive"))
      (node (ref "R326") (pin "2") (pinfunction "2_2") (pintype "passive"))
      (node (ref "R327") (pin "2") (pinfunction "2_2") (pintype "passive"))
    )
    (net (code "27") (name "Net-(R356-Pad2)") (class "Default")
      (node (ref "R356") (pin "2") (pinfunction "2_2") (pintype "passive"))
      (node (ref "R357") (pin "2") (pinfunction "2_2") (pintype "passive"))
      (node (ref "R358") (pin "2") (pinfunction "2_2") (pintype "passive"))
      (node (ref "R359") (pin "1") (pinfunction "1_1") (pintype "passive"))
    )
    (net (code "28") (name "Net-(U10-BST)") (class "Default")
      (node (ref "R115") (pin "1") (pinfunction "1_1") (pintype "passive"))
      (node (ref "U10") (pin "8") (pinfunction "BST_8") (pintype "passive"))
    )
    (net (code "29") (name "Net-(U10-EN)") (class "Default")
      (node (ref "R175") (pin "1") (pinfunction "1_1") (pintype "passive"))
      (node (ref "R177") (pin "2") (pinfunction "2_2") (pintype "passive"))
      (node (ref "U10") (pin "11") (pinfunction "EN_11") (pintype "passive"))
    )
    (net (code "30") (name "Net-(U10-PG)") (class "Default")
      (node (ref "R182") (pin "1") (pinfunction "1_1") (pintype "passive"))
      (node (ref "U10") (pin "3") (pinfunction "PG_3") (pintype "passive"))
    )
    (net (code "31") (name "SARADC_VIN7_1V8") (class "Default")
      (node (ref "R178") (pin "1") (pinfunction "1_1") (pintype "passive"))
    )
    (net (code "32") (name "VCC3V3_SYS") (class "Default")
      (node (ref "C156") (pin "1") (pinfunction "A_1") (pintype "passive"))
      (node (ref "C159") (pin "1") (pinfunction "A_1") (pintype "passive"))
      (node (ref "C160") (pin "1") (pinfunction "A_1") (pintype "passive"))
      (node (ref "C164") (pin "1") (pinfunction "A_1") (pintype "passive"))
      (node (ref "L15") (pin "2") (pinfunction "2_2") (pintype "passive"))
      (node (ref "Q12") (pin "2") (pinfunction "S_2") (pintype "passive"))
      (node (ref "R164") (pin "2") (pinfunction "2_2") (pintype "passive"))
      (node (ref "R187") (pin "1") (pinfunction "1_1") (pintype "passive"))
      (node (ref "R206") (pin "2") (pinfunction "2_2") (pintype "passive"))
    )
    (net (code "33") (name "VCC5V") (class "Default")
      (node (ref "C78") (pin "1") (pinfunction "A_1") (pintype "passive"))
      (node (ref "C79") (pin "1") (pinfunction "A_1") (pintype "passive"))
      (node (ref "J4") (pin "4") (pinfunction "4_4") (pintype "passive"))
      (node (ref "R18") (pin "2") (pinfunction "2_2") (pintype "passive"))
    )
    (net (code "34") (name "VCC12V") (class "Default")
      (node (ref "C83") (pin "1") (pinfunction "A_1") (pintype "passive"))
      (node (ref "C84") (pin "1") (pinfunction "A_1") (pintype "passive"))
      (node (ref "C89") (pin "1") (pinfunction "A_1") (pintype "passive"))
      (node (ref "J4") (pin "1") (pinfunction "1_1") (pintype "passive"))
      (node (ref "Q1") (pin "2") (pinfunction "S_2") (pintype "passive"))
      (node (ref "R1") (pin "1") (pinfunction "1_1") (pintype "passive"))
      (node (ref "R17") (pin "2") (pinfunction "2_2") (pintype "passive"))
      (node (ref "R5") (pin "2") (pinfunction "2_2") (pintype "passive"))
      (node (ref "U10") (pin "1") (pinfunction "VIN_1") (pintype "passive"))
    )
    (net (code "35") (name "VCC12V_DCIN") (class "Default")
      (node (ref "C155") (pin "1") (pinfunction "A_1") (pintype "passive"))
      (node (ref "C161") (pin "2") (pinfunction "B_2") (pintype "passive"))
      (node (ref "C162") (pin "1") (pinfunction "A_1") (pintype "passive"))
      (node (ref "D4") (pin "2") (pinfunction "K_2") (pintype "passive"))
      (node (ref "D5") (pin "2") (pinfunction "CATHODE_2") (pintype "passive"))
      (node (ref "R17") (pin "1") (pinfunction "1_1") (pintype "passive"))
      (node (ref "R176") (pin "2") (pinfunction "2_2") (pintype "passive"))
    )
    (net (code "36") (name "VCC_3V3_S0") (class "Default")
      (node (ref "R204") (pin "1") (pinfunction "1_1") (pintype "passive"))
      (node (ref "R327") (pin "1") (pinfunction "1_1") (pintype "passive"))
      (node (ref "R357") (pin "1") (pinfunction "1_1") (pintype "passive"))
    )
    (net (code "37") (name "VCC_LDO5V") (class "Default")
      (node (ref "P1") (pin "1") (pinfunction "1_1") (pintype "passive"))
      (node (ref "R181") (pin "1") (pinfunction "1_1") (pintype "passive"))
    )
    (net (code "38") (name "unconnected-(H1-Pad1)") (class "Default")
      (node (ref "H1") (pin "1") (pinfunction "1_1") (pintype "passive+no_connect"))
    )
    (net (code "39") (name "unconnected-(H2-Pad1)") (class "Default")
      (node (ref "H2") (pin "1") (pinfunction "1_1") (pintype "passive+no_connect"))
    )
    (net (code "40") (name "unconnected-(H3-Pad1)") (class "Default")
      (node (ref "H3") (pin "1") (pinfunction "1_1") (pintype "passive+no_connect"))
    )
    (net (code "41") (name "unconnected-(H4-Pad1)") (class "Default")
      (node (ref "H4") (pin "1") (pinfunction "1_1") (pintype "passive+no_connect"))
    )
    (net (code "42") (name "unconnected-(H5-Pad1)") (class "Default")
      (node (ref "H5") (pin "1") (pinfunction "1_1") (pintype "passive+no_connect"))
    )
    (net (code "43") (name "unconnected-(H6-Pad1)") (class "Default")
      (node (ref "H6") (pin "1") (pinfunction "1_1") (pintype "passive+no_connect"))
    )
    (net (code "44") (name "unconnected-(H7-Pad1)") (class "Default")
      (node (ref "H7") (pin "1") (pinfunction "1_1") (pintype "passive+no_connect"))
    )
    (net (code "45") (name "unconnected-(H8-Pad1)") (class "Default")
      (node (ref "H8") (pin "1") (pinfunction "1_1") (pintype "passive+no_connect"))
    )
    (net (code "46") (name "unconnected-(M1-Pad1)") (class "Default")
      (node (ref "M1") (pin "1") (pinfunction "1_1") (pintype "passive+no_connect"))
    )
    (net (code "47") (name "unconnected-(M2-Pad1)") (class "Default")
      (node (ref "M2") (pin "1") (pinfunction "1_1") (pintype "passive+no_connect"))
    )
    (net (code "48") (name "unconnected-(M3-Pad1)") (class "Default")
      (node (ref "M3") (pin "1") (pinfunction "1_1") (pintype "passive+no_connect"))
    )
    (net (code "49") (name "unconnected-(M4-Pad1)") (class "Default")
      (node (ref "M4") (pin "1") (pinfunction "1_1") (pintype "passive+no_connect"))
    )
    (net (code "50") (name "unconnected-(U10-EN_LDO-Pad12)") (class "Default")
      (node (ref "U10") (pin "12") (pinfunction "EN_LDO_12") (pintype "passive+no_connect"))
    )
    (net (code "51") (name "unconnected-(U10-NC-Pad4)") (class "Default")
      (node (ref "U10") (pin "4") (pinfunction "NC_4") (pintype "passive+no_connect"))
    )
  )
)
